# spirit1_868.net
KiCad netlist of a schematic drawn in Altium Designer
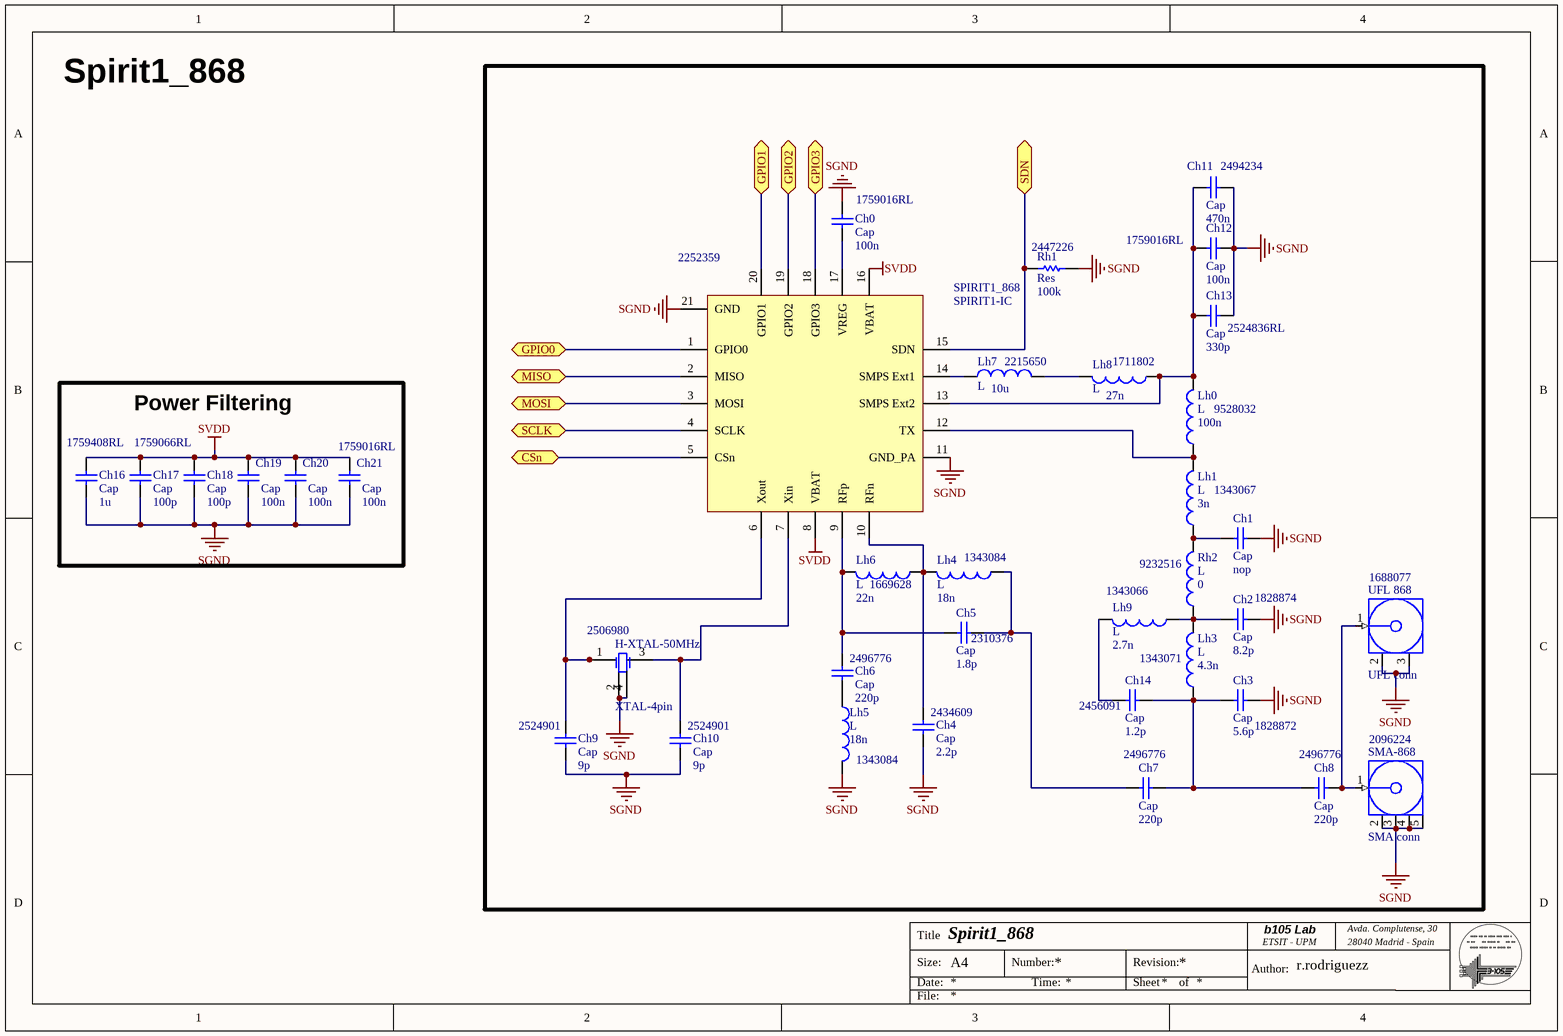
[diagram p0: spirit1_868.SchDoc]

(export (version "E")
  (design (tool "Eeschema 10.0.6"))
  (components
    (comp (ref "Ch0")
      (value "Cap")
      (footprint "0603 Cap")
      (fields
        (field (name "ALTIUM_VALUE") "100n")
        (field (name "SUPPLIER PART NUMBER 1") "1759016RL")
        (field (name "MANUFACTURER") "MULTICOMP")
        (field (name "MANUFACTURER PART NUMBER") "MC0603B104K160CT")
      )
      (libsource (lib "B105lib") (part "Cap"))
    )
    (comp (ref "Ch1")
      (value "Cap")
      (footprint "0402 CAP")
      (fields (field (name "ALTIUM_VALUE") "nop"))
      (libsource (lib "B105lib") (part "Cap"))
    )
    (comp (ref "Ch2")
      (value "Cap")
      (footprint "0402 CAP")
      (fields
        (field (name "ALTIUM_VALUE") "8.2p")
        (field (name "SUPPLIER PART NUMBER 1") "1828874")
        (field (name "MANUFACTURER") "MURATA")
        (field (name "MANUFACTURER PART NUMBER") "GRM1555C1H8R2CA01D")
      )
      (libsource (lib "B105lib") (part "Cap"))
    )
    (comp (ref "Ch3")
      (value "Cap")
      (footprint "0402 CAP")
      (fields
        (field (name "ALTIUM_VALUE") "5.6p")
        (field (name "SUPPLIER PART NUMBER 1") "1828872")
        (field (name "MANUFACTURER") "MURATA")
        (field (name "MANUFACTURER PART NUMBER") "GRM1555C1H5R6CA01D")
      )
      (libsource (lib "B105lib") (part "Cap"))
    )
    (comp (ref "Ch4")
      (value "Cap")
      (footprint "0402 CAP")
      (fields
        (field (name "ALTIUM_VALUE") "2.2p")
        (field (name "SUPPLIER PART NUMBER 1") "2434609")
        (field (name "MANUFACTURER") "MURATA")
        (field (name "MANUFACTURER PART NUMBER") "GRM1555C1H2R2CA01D")
      )
      (libsource (lib "B105lib") (part "Cap"))
    )
    (comp (ref "Ch5")
      (value "Cap")
      (footprint "0402 CAP")
      (fields
        (field (name "ALTIUM_VALUE") "1.8p")
        (field (name "SUPPLIER PART NUMBER 1") "2310376")
        (field (name "MANUFACTURER") "MULTICOMP")
        (field (name "MANUFACTURER PART NUMBER") "MCRF15N1R8A500CT")
      )
      (libsource (lib "B105lib") (part "Cap"))
    )
    (comp (ref "Ch6")
      (value "Cap")
      (footprint "0402 CAP")
      (fields
        (field (name "ALTIUM_VALUE") "220p")
        (field (name "SUPPLIER PART NUMBER 1") "2496776")
        (field (name "MANUFACTURER") "WALSIN")
        (field (name "MANUFACTURER PART NUMBER") "0402B221K500CT")
      )
      (libsource (lib "B105lib") (part "Cap"))
    )
    (comp (ref "Ch7")
      (value "Cap")
      (footprint "0402 CAP")
      (fields
        (field (name "ALTIUM_VALUE") "220p")
        (field (name "SUPPLIER PART NUMBER 1") "2496776")
        (field (name "MANUFACTURER") "WALSIN")
        (field (name "MANUFACTURER PART NUMBER") "0402B221K500CT")
      )
      (libsource (lib "B105lib") (part "Cap"))
    )
    (comp (ref "Ch8")
      (value "Cap")
      (footprint "0402 CAP")
      (fields
        (field (name "ALTIUM_VALUE") "220p")
        (field (name "SUPPLIER PART NUMBER 1") "2496776")
        (field (name "MANUFACTURER") "WALSIN")
        (field (name "MANUFACTURER PART NUMBER") "0402B221K500CT")
      )
      (libsource (lib "B105lib") (part "Cap"))
    )
    (comp (ref "Ch9")
      (value "Cap")
      (footprint "0603 Cap")
      (fields
        (field (name "ALTIUM_VALUE") "9p")
        (field (name "SUPPLIER PART NUMBER 1") "2524901")
        (field (name "MANUFACTURER") "WALSIN")
        (field (name "MANUFACTURER PART NUMBER") "0603N9R0D500CT")
      )
      (libsource (lib "B105lib") (part "Cap"))
    )
    (comp (ref "Ch10")
      (value "Cap")
      (footprint "0603 Cap")
      (fields
        (field (name "ALTIUM_VALUE") "9p")
        (field (name "SUPPLIER PART NUMBER 1") "2524901")
        (field (name "MANUFACTURER") "WALSIN")
        (field (name "MANUFACTURER PART NUMBER") "0603N9R0D500CT")
      )
      (libsource (lib "B105lib") (part "Cap"))
    )
    (comp (ref "Ch11")
      (value "Cap")
      (footprint "0603 Cap")
      (fields
        (field (name "ALTIUM_VALUE") "470n")
        (field (name "SUPPLIER PART NUMBER 1") "2494234")
        (field (name "MANUFACTURER") "MURATA")
        (field (name "MANUFACTURER PART NUMBER") "GRM188R61E474KA12D")
      )
      (libsource (lib "B105lib") (part "Cap"))
    )
    (comp (ref "Ch12")
      (value "Cap")
      (footprint "0603 Cap")
      (fields
        (field (name "ALTIUM_VALUE") "100n")
        (field (name "SUPPLIER PART NUMBER 1") "1759016RL")
        (field (name "MANUFACTURER") "MULTICOMP")
        (field (name "MANUFACTURER PART NUMBER") "MC0603B104K160CT")
      )
      (libsource (lib "B105lib") (part "Cap"))
    )
    (comp (ref "Ch13")
      (value "Cap")
      (footprint "0603 Cap")
      (fields
        (field (name "ALTIUM_VALUE") "330p")
        (field (name "SUPPLIER PART NUMBER 1") "2524836RL")
        (field (name "MANUFACTURER") "WALSIN")
        (field (name "MANUFACTURER PART NUMBER") "0603B331K500CT")
      )
      (libsource (lib "B105lib") (part "Cap"))
    )
    (comp (ref "Ch14")
      (value "Cap")
      (footprint "0402 CAP")
      (fields
        (field (name "ALTIUM_VALUE") "1.2p")
        (field (name "SUPPLIER PART NUMBER 1") "2456091")
        (field (name "MANUFACTURER") "MURATA")
        (field (name "MANUFACTURER PART NUMBER") "GRM1555C1H1R2BA01D")
      )
      (libsource (lib "B105lib") (part "Cap"))
    )
    (comp (ref "Ch16")
      (value "Cap")
      (footprint "0603 Cap")
      (fields
        (field (name "ALTIUM_VALUE") "1u")
        (field (name "SUPPLIER PART NUMBER 1") "1759408RL")
        (field (name "MANUFACTURER") "MULTICOMP")
        (field (name "MANUFACTURER PART NUMBER") "MC0603F105Z160CT")
      )
      (libsource (lib "B105lib") (part "Cap"))
    )
    (comp (ref "Ch17")
      (value "Cap")
      (footprint "0603 Cap")
      (fields
        (field (name "ALTIUM_VALUE") "100p")
        (field (name "SUPPLIER PART NUMBER 1") "1759066RL")
        (field (name "MANUFACTURER") "MULTICOMP")
        (field (name "MANUFACTURER PART NUMBER") "MC0603N101J500CT")
      )
      (libsource (lib "B105lib") (part "Cap"))
    )
    (comp (ref "Ch18")
      (value "Cap")
      (footprint "0603 Cap")
      (fields
        (field (name "ALTIUM_VALUE") "100p")
        (field (name "MANUFACTURER") "MULTICOMP")
        (field (name "MANUFACTURER PART NUMBER") "MC0603N101J500CT")
      )
      (libsource (lib "B105lib") (part "Cap"))
    )
    (comp (ref "Ch19")
      (value "Cap")
      (footprint "0603 Cap")
      (fields
        (field (name "ALTIUM_VALUE") "100n")
        (field (name "MANUFACTURER") "MULTICOMP")
        (field (name "MANUFACTURER PART NUMBER") "MC0603B104K160CT")
      )
      (libsource (lib "B105lib") (part "Cap"))
    )
    (comp (ref "Ch20")
      (value "Cap")
      (footprint "0603 Cap")
      (fields
        (field (name "ALTIUM_VALUE") "100n")
        (field (name "MANUFACTURER") "MULTICOMP")
        (field (name "MANUFACTURER PART NUMBER") "MC0603B104K160CT")
      )
      (libsource (lib "B105lib") (part "Cap"))
    )
    (comp (ref "Ch21")
      (value "Cap")
      (footprint "0603 Cap")
      (fields
        (field (name "ALTIUM_VALUE") "100n")
        (field (name "SUPPLIER PART NUMBER 1") "1759016RL")
        (field (name "MANUFACTURER") "MULTICOMP")
        (field (name "MANUFACTURER PART NUMBER") "MC0603B104K160CT")
      )
      (libsource (lib "B105lib") (part "Cap"))
    )
    (comp (ref "H-XTAL-50MHz")
      (value "XTAL-4pin")
      (footprint "XTAL-4PIN-2mmx1.6mm")
      (fields
        (field (name "SUPPLIER PART NUMBER 1") "2506980")
        (field (name "MANUFACTURER") "EPSON")
        (field (name "MANUFACTURER PART NUMBER") "X1E000351002812")
      )
      (libsource (lib "B105lib") (part "XTAL-4pin"))
    )
    (comp (ref "Lh0")
      (value "L")
      (footprint "0603 IND")
      (fields
        (field (name "ALTIUM_VALUE") "100n")
        (field (name "SUPPLIER PART NUMBER 1") "9528032")
        (field (name "MANUFACTURER") "MURATA")
        (field (name "MANUFACTURER PART NUMBER") "LQW18ANR10G00D")
      )
      (libsource (lib "B105lib") (part "Ind"))
    )
    (comp (ref "Lh1")
      (value "L")
      (footprint "0402 IND")
      (fields
        (field (name "ALTIUM_VALUE") "3n")
        (field (name "SUPPLIER PART NUMBER 1") "1343067")
        (field (name "MANUFACTURER") "MURATA")
        (field (name "MANUFACTURER PART NUMBER") "LQG15HN3N0S02D")
      )
      (libsource (lib "B105lib") (part "Ind"))
    )
    (comp (ref "Lh3")
      (value "L")
      (footprint "0402 IND")
      (fields
        (field (name "ALTIUM_VALUE") "4.3n")
        (field (name "SUPPLIER PART NUMBER 1") "1343071")
        (field (name "MANUFACTURER") "MURATA")
        (field (name "MANUFACTURER PART NUMBER") "LQG15HN4N3S02D")
      )
      (libsource (lib "B105lib") (part "Ind"))
    )
    (comp (ref "Lh4")
      (value "L")
      (footprint "0402 IND")
      (fields
        (field (name "ALTIUM_VALUE") "18n")
        (field (name "SUPPLIER PART NUMBER 1") "1343084")
        (field (name "MANUFACTURER") "MURATA")
        (field (name "MANUFACTURER PART NUMBER") "LQG15HN18NJ02D")
      )
      (libsource (lib "B105lib") (part "Ind"))
    )
    (comp (ref "Lh5")
      (value "L")
      (footprint "0402 IND")
      (fields
        (field (name "ALTIUM_VALUE") "18n")
        (field (name "SUPPLIER PART NUMBER 1") "1343084")
        (field (name "MANUFACTURER") "MURATA")
        (field (name "MANUFACTURER PART NUMBER") "LQG15HN18NJ02D")
      )
      (libsource (lib "B105lib") (part "Ind"))
    )
    (comp (ref "Lh6")
      (value "L")
      (footprint "0402 IND")
      (fields
        (field (name "ALTIUM_VALUE") "22n")
        (field (name "SUPPLIER PART NUMBER 1") "1669628")
        (field (name "MANUFACTURER") "TDK")
        (field (name "MANUFACTURER PART NUMBER") "MLK1005S22NJ")
      )
      (libsource (lib "B105lib") (part "Ind"))
    )
    (comp (ref "Lh7")
      (value "L")
      (footprint "0805 Ind")
      (fields
        (field (name "ALTIUM_VALUE") "10u")
        (field (name "SUPPLIER PART NUMBER 1") "2215650")
        (field (name "MANUFACTURER") "TDK")
        (field (name "MANUFACTURER PART NUMBER") "MLZ2012M100WT")
      )
      (libsource (lib "B105lib") (part "Ind"))
    )
    (comp (ref "Lh8")
      (value "L")
      (footprint "0603 IND")
      (fields
        (field (name "ALTIUM_VALUE") "27n")
        (field (name "SUPPLIER PART NUMBER 1") "1711802")
        (field (name "MANUFACTURER") "MULTICOMP")
        (field (name "MANUFACTURER PART NUMBER") "MCFT000088")
      )
      (libsource (lib "B105lib") (part "Ind"))
    )
    (comp (ref "Lh9")
      (value "L")
      (footprint "0402 IND")
      (fields
        (field (name "ALTIUM_VALUE") "2.7n")
        (field (name "SUPPLIER PART NUMBER 1") "1343066")
        (field (name "MANUFACTURER") "MURATA")
        (field (name "MANUFACTURER PART NUMBER") "LQG15HN2N7S02D")
      )
      (libsource (lib "B105lib") (part "Ind"))
    )
    (comp (ref "Rh1")
      (value "Res")
      (footprint "0603 Res")
      (fields
        (field (name "ALTIUM_VALUE") "100k")
        (field (name "SUPPLIER PART NUMBER 1") "2447226")
        (field (name "MANUFACTURER") "MULTICOMP")
        (field (name "MANUFACTURER PART NUMBER") "MCWR06X1003FTL")
      )
      (libsource (lib "B105lib") (part "Res"))
    )
    (comp (ref "Rh2")
      (value "L")
      (footprint "0402 IND")
      (fields
        (field (name "ALTIUM_VALUE") "0")
        (field (name "SUPPLIER PART NUMBER 1") "9232516")
        (field (name "MANUFACTURER") "YAGEO (PHYCOMP)")
        (field (name "MANUFACTURER PART NUMBER") "RC0402JR-070RL")
      )
      (libsource (lib "B105lib") (part "Ind"))
    )
    (comp (ref "SMA-868")
      (value "SMA conn")
      (footprint "SMA-conn")
      (fields
        (field (name "SUPPLIER PART NUMBER 1") "2096224")
        (field (name "MANUFACTURER") "LPRS")
        (field (name "MANUFACTURER PART NUMBER") "SMA RA CONNECTOR")
      )
      (libsource (lib "B105lib") (part "SMA conn"))
    )
    (comp (ref "SPIRIT1_868")
      (value "SPIRIT1-IC")
      (footprint "QFN-20")
      (fields
        (field (name "SUPPLIER PART NUMBER 1") "2252359")
        (field (name "MANUFACTURER") "STMICROELECTRONICS")
        (field (name "MANUFACTURER PART NUMBER") "SPIRIT1QTR")
      )
      (libsource (lib "B105lib") (part "SPIRIT1-IC"))
    )
    (comp (ref "UFL 868")
      (value "UFL conn")
      (footprint "UFL conn")
      (fields
        (field (name "SUPPLIER PART NUMBER 1") "1688077")
        (field (name "MANUFACTURER") "HIROSE(HRS)")
        (field (name "MANUFACTURER PART NUMBER") "U.FL-R-SMT-1(10)")
      )
      (libsource (lib "B105lib") (part "UFL conn"))
    )
  )
  (nets
    (net (code "1") (name "/CSn") (class "Default")
      (node (ref "SPIRIT1_868") (pin "5") (pinfunction "CSn_5") (pintype "passive"))
    )
    (net (code "2") (name "/GPIO0") (class "Default")
      (node (ref "SPIRIT1_868") (pin "1") (pinfunction "GPIO0_1") (pintype "passive"))
    )
    (net (code "3") (name "/GPIO1") (class "Default")
      (node (ref "SPIRIT1_868") (pin "20") (pinfunction "GPIO1_20") (pintype "passive"))
    )
    (net (code "4") (name "/GPIO2") (class "Default")
      (node (ref "SPIRIT1_868") (pin "19") (pinfunction "GPIO2_19") (pintype "passive"))
    )
    (net (code "5") (name "/GPIO3") (class "Default")
      (node (ref "SPIRIT1_868") (pin "18") (pinfunction "GPIO3_18") (pintype "passive"))
    )
    (net (code "6") (name "/MISO") (class "Default")
      (node (ref "SPIRIT1_868") (pin "2") (pinfunction "MISO_2") (pintype "passive"))
    )
    (net (code "7") (name "/MOSI") (class "Default")
      (node (ref "SPIRIT1_868") (pin "3") (pinfunction "MOSI_3") (pintype "passive"))
    )
    (net (code "8") (name "/SCLK") (class "Default")
      (node (ref "SPIRIT1_868") (pin "4") (pinfunction "SCLK_4") (pintype "passive"))
    )
    (net (code "9") (name "/SDN") (class "Default")
      (node (ref "Rh1") (pin "1") (pinfunction "1_1") (pintype "passive"))
      (node (ref "SPIRIT1_868") (pin "15") (pinfunction "SDN_15") (pintype "passive"))
    )
    (net (code "10") (name "Net-(Ch1-Pad2)") (class "Default")
      (node (ref "Ch1") (pin "2") (pinfunction "2_2") (pintype "passive"))
      (node (ref "Lh1") (pin "1") (pinfunction "1_1") (pintype "passive"))
      (node (ref "Rh2") (pin "2") (pinfunction "2_2") (pintype "passive"))
    )
    (net (code "11") (name "Net-(Ch2-Pad2)") (class "Default")
      (node (ref "Ch2") (pin "2") (pinfunction "2_2") (pintype "passive"))
      (node (ref "Lh3") (pin "2") (pinfunction "2_2") (pintype "passive"))
      (node (ref "Lh9") (pin "1") (pinfunction "1_1") (pintype "passive"))
      (node (ref "Rh2") (pin "1") (pinfunction "1_1") (pintype "passive"))
    )
    (net (code "12") (name "Net-(Ch5-Pad1)") (class "Default")
      (node (ref "Ch5") (pin "1") (pinfunction "1_1") (pintype "passive"))
      (node (ref "Ch7") (pin "1") (pinfunction "1_1") (pintype "passive"))
      (node (ref "Lh4") (pin "1") (pinfunction "1_1") (pintype "passive"))
    )
    (net (code "13") (name "Net-(Ch6-Pad2)") (class "Default")
      (node (ref "Ch6") (pin "2") (pinfunction "2_2") (pintype "passive"))
      (node (ref "Lh5") (pin "1") (pinfunction "1_1") (pintype "passive"))
    )
    (net (code "14") (name "Net-(Ch14-Pad1)") (class "Default")
      (node (ref "Ch14") (pin "1") (pinfunction "1_1") (pintype "passive"))
      (node (ref "Ch3") (pin "2") (pinfunction "2_2") (pintype "passive"))
      (node (ref "Ch7") (pin "2") (pinfunction "2_2") (pintype "passive"))
      (node (ref "Ch8") (pin "1") (pinfunction "1_1") (pintype "passive"))
      (node (ref "Lh3") (pin "1") (pinfunction "1_1") (pintype "passive"))
    )
    (net (code "15") (name "Net-(Ch14-Pad2)") (class "Default")
      (node (ref "Ch14") (pin "2") (pinfunction "2_2") (pintype "passive"))
      (node (ref "Lh9") (pin "2") (pinfunction "2_2") (pintype "passive"))
    )
    (net (code "16") (name "Net-(H-XTAL-50MHz-OSC1)") (class "Default")
      (node (ref "Ch9") (pin "2") (pinfunction "2_2") (pintype "passive"))
      (node (ref "H-XTAL-50MHz") (pin "1") (pinfunction "OSC1_1") (pintype "passive"))
      (node (ref "SPIRIT1_868") (pin "6") (pinfunction "Xout_6") (pintype "passive"))
    )
    (net (code "17") (name "Net-(H-XTAL-50MHz-OSC2)") (class "Default")
      (node (ref "Ch10") (pin "2") (pinfunction "2_2") (pintype "passive"))
      (node (ref "H-XTAL-50MHz") (pin "3") (pinfunction "OSC2_3") (pintype "passive"))
      (node (ref "SPIRIT1_868") (pin "7") (pinfunction "Xin_7") (pintype "passive"))
    )
    (net (code "18") (name "Net-(Lh7-Pad2)") (class "Default")
      (node (ref "Lh7") (pin "2") (pinfunction "2_2") (pintype "passive"))
      (node (ref "Lh8") (pin "2") (pinfunction "2_2") (pintype "passive"))
    )
    (net (code "19") (name "Net-(SMA-868-Signal)") (class "Default")
      (node (ref "Ch8") (pin "2") (pinfunction "2_2") (pintype "passive"))
      (node (ref "SMA-868") (pin "1") (pinfunction "Signal_1") (pintype "input"))
      (node (ref "UFL 868") (pin "1") (pinfunction "Signal_1") (pintype "input"))
    )
    (net (code "20") (name "Net-(SPIRIT1_868-RFn)") (class "Default")
      (node (ref "Ch4") (pin "2") (pinfunction "2_2") (pintype "passive"))
      (node (ref "Lh4") (pin "2") (pinfunction "2_2") (pintype "passive"))
      (node (ref "Lh6") (pin "1") (pinfunction "1_1") (pintype "passive"))
      (node (ref "SPIRIT1_868") (pin "10") (pinfunction "RFn_10") (pintype "passive"))
    )
    (net (code "21") (name "Net-(SPIRIT1_868-RFp)") (class "Default")
      (node (ref "Ch5") (pin "2") (pinfunction "2_2") (pintype "passive"))
      (node (ref "Ch6") (pin "1") (pinfunction "1_1") (pintype "passive"))
      (node (ref "Lh6") (pin "2") (pinfunction "2_2") (pintype "passive"))
      (node (ref "SPIRIT1_868") (pin "9") (pinfunction "RFp_9") (pintype "passive"))
    )
    (net (code "22") (name "Net-(SPIRIT1_868-SMPS_Ext1)") (class "Default")
      (node (ref "Lh7") (pin "1") (pinfunction "1_1") (pintype "passive"))
      (node (ref "SPIRIT1_868") (pin "14") (pinfunction "SMPS_Ext1_14") (pintype "passive"))
    )
    (net (code "23") (name "Net-(SPIRIT1_868-SMPS_Ext2)") (class "Default")
      (node (ref "Ch11") (pin "2") (pinfunction "2_2") (pintype "passive"))
      (node (ref "Ch12") (pin "2") (pinfunction "2_2") (pintype "passive"))
      (node (ref "Ch13") (pin "2") (pinfunction "2_2") (pintype "passive"))
      (node (ref "Lh0") (pin "2") (pinfunction "2_2") (pintype "passive"))
      (node (ref "Lh8") (pin "1") (pinfunction "1_1") (pintype "passive"))
      (node (ref "SPIRIT1_868") (pin "13") (pinfunction "SMPS_Ext2_13") (pintype "passive"))
    )
    (net (code "24") (name "Net-(SPIRIT1_868-TX)") (class "Default")
      (node (ref "Lh0") (pin "1") (pinfunction "1_1") (pintype "passive"))
      (node (ref "Lh1") (pin "2") (pinfunction "2_2") (pintype "passive"))
      (node (ref "SPIRIT1_868") (pin "12") (pinfunction "TX_12") (pintype "passive"))
    )
    (net (code "25") (name "Net-(SPIRIT1_868-VREG)") (class "Default")
      (node (ref "Ch0") (pin "1") (pinfunction "1_1") (pintype "passive"))
      (node (ref "SPIRIT1_868") (pin "17") (pinfunction "VREG_17") (pintype "passive"))
    )
    (net (code "26") (name "SGND") (class "Default")
      (node (ref "Ch0") (pin "2") (pinfunction "2_2") (pintype "passive"))
      (node (ref "Ch1") (pin "1") (pinfunction "1_1") (pintype "passive"))
      (node (ref "Ch10") (pin "1") (pinfunction "1_1") (pintype "passive"))
      (node (ref "Ch11") (pin "1") (pinfunction "1_1") (pintype "passive"))
      (node (ref "Ch12") (pin "1") (pinfunction "1_1") (pintype "passive"))
      (node (ref "Ch13") (pin "1") (pinfunction "1_1") (pintype "passive"))
      (node (ref "Ch16") (pin "1") (pinfunction "1_1") (pintype "passive"))
      (node (ref "Ch17") (pin "1") (pinfunction "1_1") (pintype "passive"))
      (node (ref "Ch18") (pin "1") (pinfunction "1_1") (pintype "passive"))
      (node (ref "Ch19") (pin "1") (pinfunction "1_1") (pintype "passive"))
      (node (ref "Ch2") (pin "1") (pinfunction "1_1") (pintype "passive"))
      (node (ref "Ch20") (pin "1") (pinfunction "1_1") (pintype "passive"))
      (node (ref "Ch21") (pin "1") (pinfunction "1_1") (pintype "passive"))
      (node (ref "Ch3") (pin "1") (pinfunction "1_1") (pintype "passive"))
      (node (ref "Ch4") (pin "1") (pinfunction "1_1") (pintype "passive"))
      (node (ref "Ch9") (pin "1") (pinfunction "1_1") (pintype "passive"))
      (node (ref "H-XTAL-50MHz") (pin "2") (pinfunction "GND_2") (pintype "passive"))
      (node (ref "H-XTAL-50MHz") (pin "4") (pinfunction "GND_4") (pintype "passive"))
      (node (ref "Lh5") (pin "2") (pinfunction "2_2") (pintype "passive"))
      (node (ref "Rh1") (pin "2") (pinfunction "2_2") (pintype "passive"))
      (node (ref "SMA-868") (pin "2") (pinfunction "GND_2") (pintype "power_in"))
      (node (ref "SMA-868") (pin "3") (pinfunction "GND_3") (pintype "power_in"))
      (node (ref "SMA-868") (pin "4") (pinfunction "GND_4") (pintype "power_in"))
      (node (ref "SMA-868") (pin "5") (pinfunction "GND_5") (pintype "power_in"))
      (node (ref "SPIRIT1_868") (pin "11") (pinfunction "GND_PA_11") (pintype "passive"))
      (node (ref "SPIRIT1_868") (pin "21") (pinfunction "GND_21") (pintype "passive"))
      (node (ref "UFL 868") (pin "2") (pinfunction "GND_2") (pintype "power_in"))
      (node (ref "UFL 868") (pin "3") (pinfunction "GND_3") (pintype "power_in"))
    )
    (net (code "27") (name "SVDD") (class "Default")
      (node (ref "Ch16") (pin "2") (pinfunction "2_2") (pintype "passive"))
      (node (ref "Ch17") (pin "2") (pinfunction "2_2") (pintype "passive"))
      (node (ref "Ch18") (pin "2") (pinfunction "2_2") (pintype "passive"))
      (node (ref "Ch19") (pin "2") (pinfunction "2_2") (pintype "passive"))
      (node (ref "Ch20") (pin "2") (pinfunction "2_2") (pintype "passive"))
      (node (ref "Ch21") (pin "2") (pinfunction "2_2") (pintype "passive"))
      (node (ref "SPIRIT1_868") (pin "16") (pinfunction "VBAT_16") (pintype "passive"))
      (node (ref "SPIRIT1_868") (pin "8") (pinfunction "VBAT_8") (pintype "passive"))
    )
  )
)
